# JackBot_skeem.net
KiCad netlist of a schematic drawn in Altium Designer
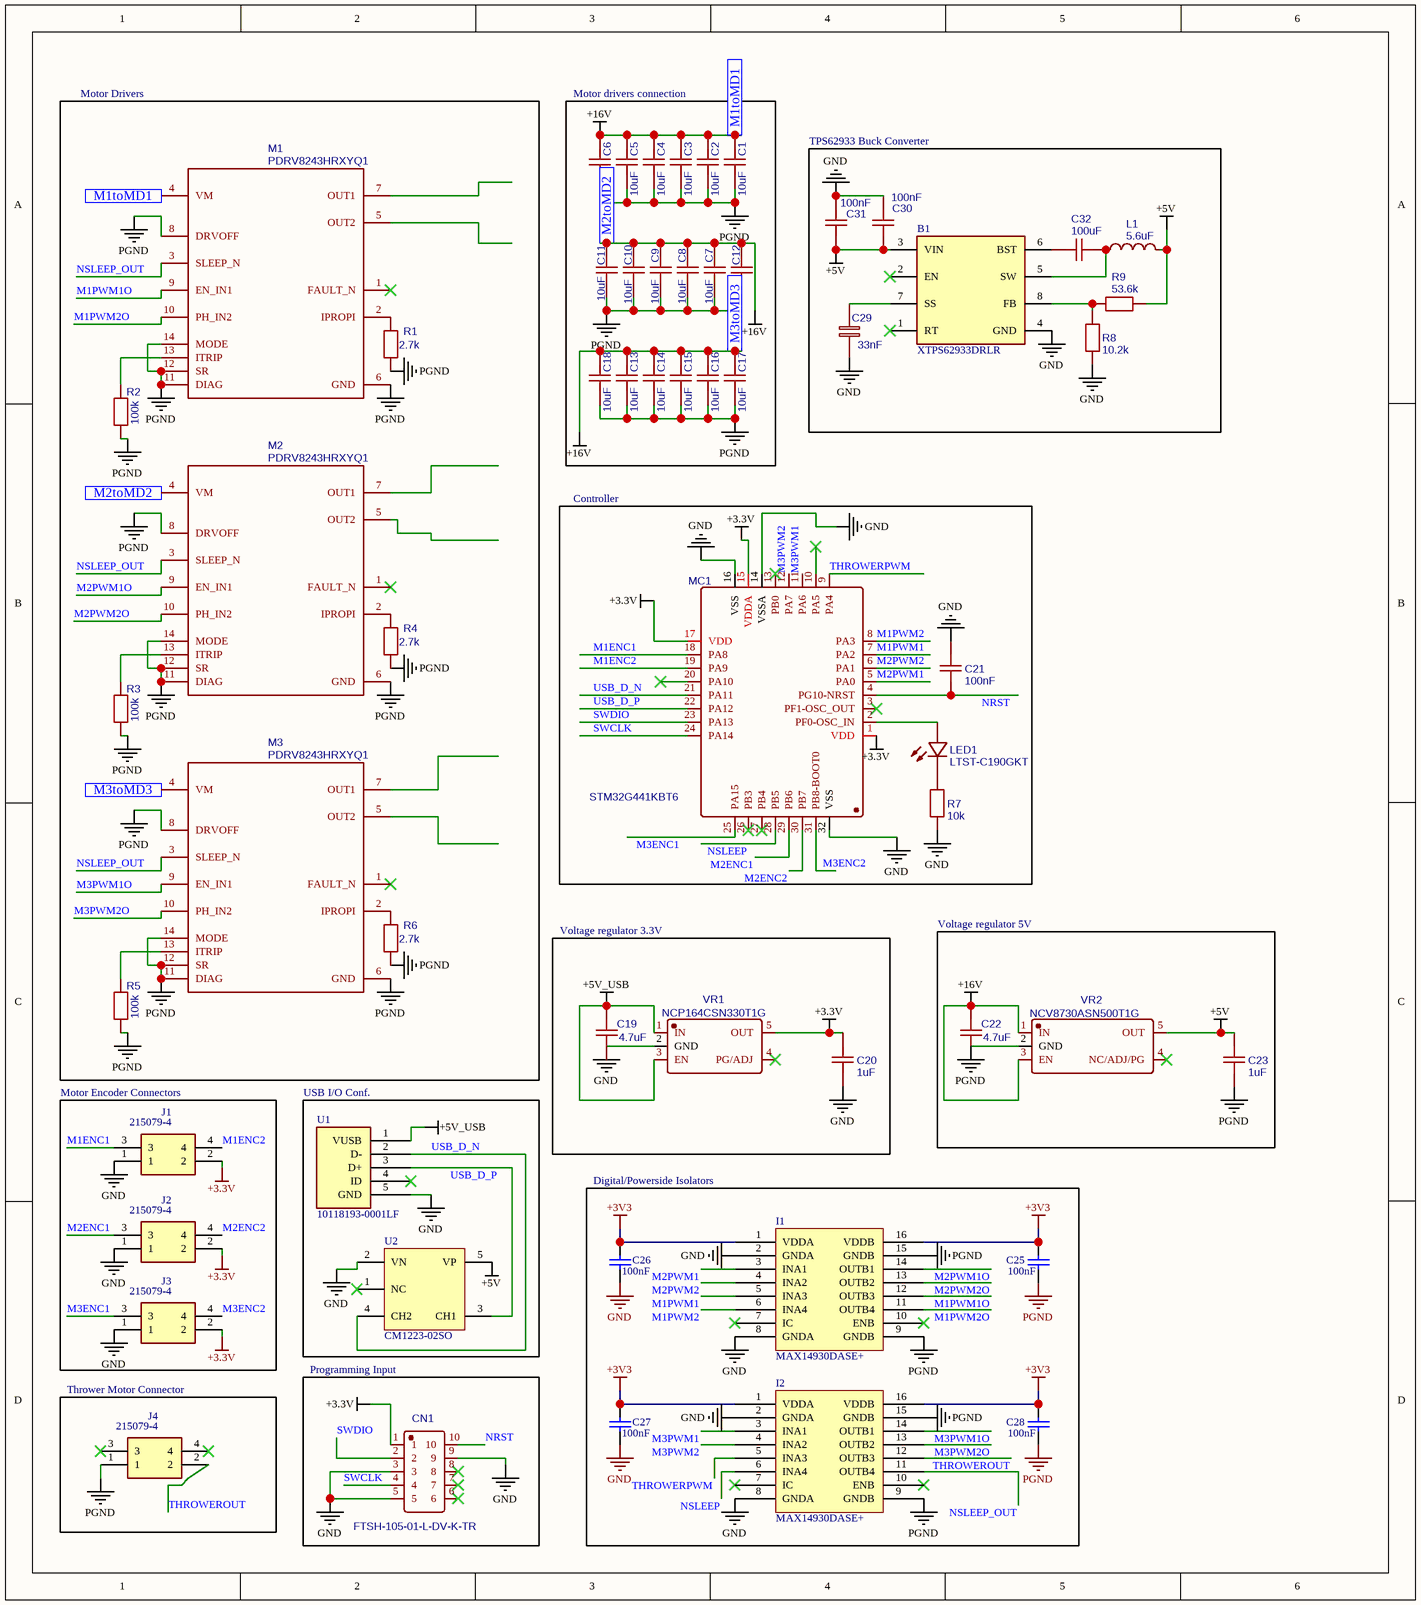
[diagram p0: JackBot_skeem.schdoc]

(export (version "E")
  (design (tool "Eeschema 10.0.6"))
  (components
    (comp (ref "B1") (value "XTPS62933DRLR") (libsource (lib "altium-import") (part "root_0_XTPS62933DRLR_")))
    (comp (ref "C1")
      (value "10uF")
      (fields (field (name "CONTRIBUTOR") "LCEDA_Lib"))
      (libsource (lib "altium-import") (part "root_3_10uF_"))
    )
    (comp (ref "C2")
      (value "10uF")
      (fields (field (name "CONTRIBUTOR") "LCEDA_Lib"))
      (libsource (lib "altium-import") (part "root_3_10uF_"))
    )
    (comp (ref "C3")
      (value "10uF")
      (fields (field (name "CONTRIBUTOR") "LCEDA_Lib"))
      (libsource (lib "altium-import") (part "root_3_10uF_"))
    )
    (comp (ref "C4")
      (value "10uF")
      (fields (field (name "CONTRIBUTOR") "LCEDA_Lib"))
      (libsource (lib "altium-import") (part "root_3_10uF_"))
    )
    (comp (ref "C5")
      (value "10uF")
      (fields (field (name "CONTRIBUTOR") "LCEDA_Lib"))
      (libsource (lib "altium-import") (part "root_3_10uF_"))
    )
    (comp (ref "C6")
      (value "10uF")
      (fields (field (name "CONTRIBUTOR") "LCEDA_Lib"))
      (libsource (lib "altium-import") (part "root_3_10uF_"))
    )
    (comp (ref "C7")
      (value "10uF")
      (fields (field (name "CONTRIBUTOR") "LCEDA_Lib"))
      (libsource (lib "") (part "root_3_10uF__1"))
    )
    (comp (ref "C8")
      (value "10uF")
      (fields (field (name "CONTRIBUTOR") "LCEDA_Lib"))
      (libsource (lib "") (part "root_3_10uF__1"))
    )
    (comp (ref "C9")
      (value "10uF")
      (fields (field (name "CONTRIBUTOR") "LCEDA_Lib"))
      (libsource (lib "") (part "root_3_10uF__1"))
    )
    (comp (ref "C10")
      (value "10uF")
      (fields (field (name "CONTRIBUTOR") "LCEDA_Lib"))
      (libsource (lib "") (part "root_3_10uF__1"))
    )
    (comp (ref "C11")
      (value "10uF")
      (fields (field (name "CONTRIBUTOR") "LCEDA_Lib"))
      (libsource (lib "") (part "root_3_10uF__1"))
    )
    (comp (ref "C12")
      (value "10uF")
      (fields (field (name "CONTRIBUTOR") "LCEDA_Lib"))
      (libsource (lib "") (part "root_3_10uF__1"))
    )
    (comp (ref "C13")
      (value "10uF")
      (fields (field (name "CONTRIBUTOR") "LCEDA_Lib"))
      (libsource (lib "altium-import") (part "root_3_10uF_"))
    )
    (comp (ref "C14")
      (value "10uF")
      (fields (field (name "CONTRIBUTOR") "LCEDA_Lib"))
      (libsource (lib "altium-import") (part "root_3_10uF_"))
    )
    (comp (ref "C15")
      (value "10uF")
      (fields (field (name "CONTRIBUTOR") "LCEDA_Lib"))
      (libsource (lib "altium-import") (part "root_3_10uF_"))
    )
    (comp (ref "C16")
      (value "10uF")
      (fields (field (name "CONTRIBUTOR") "LCEDA_Lib"))
      (libsource (lib "altium-import") (part "root_3_10uF_"))
    )
    (comp (ref "C17")
      (value "10uF")
      (fields (field (name "CONTRIBUTOR") "LCEDA_Lib"))
      (libsource (lib "altium-import") (part "root_3_10uF_"))
    )
    (comp (ref "C18")
      (value "10uF")
      (fields (field (name "CONTRIBUTOR") "LCEDA_Lib"))
      (libsource (lib "altium-import") (part "root_3_10uF_"))
    )
    (comp (ref "C19")
      (value "4.7uF")
      (fields (field (name "CONTRIBUTOR") "LCEDA_Lib"))
      (libsource (lib "altium-import") (part "root_1_4.7uF_"))
    )
    (comp (ref "C20")
      (value "1uF")
      (fields (field (name "CONTRIBUTOR") "LCEDA_Lib"))
      (libsource (lib "altium-import") (part "root_1_1uF_"))
    )
    (comp (ref "C21")
      (value "100nF")
      (fields (field (name "CONTRIBUTOR") "LCEDA_Lib"))
      (libsource (lib "altium-import") (part "root_3_100nF_"))
    )
    (comp (ref "C22")
      (value "4.7uF")
      (fields (field (name "CONTRIBUTOR") "LCEDA_Lib"))
      (libsource (lib "altium-import") (part "root_1_4.7uF_"))
    )
    (comp (ref "C23")
      (value "1uF")
      (fields (field (name "CONTRIBUTOR") "LCEDA_Lib"))
      (libsource (lib "altium-import") (part "root_1_1uF_"))
    )
    (comp (ref "C25")
      (value "100nF")
      (fields (field (name "MANUFACTURER") "Murata"))
      (libsource (lib "") (part "root_1_100nF__2"))
    )
    (comp (ref "C26")
      (value "100nF")
      (fields (field (name "MANUFACTURER") "Murata"))
      (libsource (lib "altium-import") (part "root_1_100nF_"))
    )
    (comp (ref "C27")
      (value "100nF")
      (fields (field (name "MANUFACTURER") "Murata"))
      (libsource (lib "altium-import") (part "root_1_100nF_"))
    )
    (comp (ref "C28")
      (value "100nF")
      (fields (field (name "MANUFACTURER") "Murata"))
      (libsource (lib "") (part "root_1_100nF__2"))
    )
    (comp (ref "C29")
      (value "33nF")
      (fields (field (name "CONTRIBUTOR") "LCEDA_Lib"))
      (libsource (lib "altium-import") (part "root_1_33nF_"))
    )
    (comp (ref "C30")
      (value "100nF")
      (fields (field (name "CONTRIBUTOR") "LCEDA_Lib"))
      (libsource (lib "") (part "root_1_100nF__1"))
    )
    (comp (ref "C31")
      (value "100nF")
      (fields (field (name "CONTRIBUTOR") "LCEDA_Lib"))
      (libsource (lib "") (part "root_1_100nF__1"))
    )
    (comp (ref "C32")
      (value "100uF")
      (fields (field (name "CONTRIBUTOR") "LCEDA_Lib"))
      (libsource (lib "altium-import") (part "root_2_100uF_"))
    )
    (comp (ref "CN1")
      (value "FTSH-105-01-L-DV-K-TR")
      (fields (field (name "BOM_SUPPLIER PART") "C448647") (field (name "CONTRIBUTOR") "LCSC"))
      (libsource (lib "altium-import") (part "root_0_FTSH-105-01-L-DV-K-TR_"))
    )
    (comp (ref "I1") (value "MAX14930DASE+") (libsource (lib "altium-import") (part "root_0_MAX14930DASE+_")))
    (comp (ref "I2") (value "MAX14930DASE+") (libsource (lib "altium-import") (part "root_0_MAX14930DASE+_")))
    (comp (ref "J1")
      (value "215079-4")
      (fields (field (name "MOUSER PART NUMBER") "571-215079-4"))
      (libsource (lib "altium-import") (part "root_0_215079-4_"))
    )
    (comp (ref "J2")
      (value "215079-4")
      (fields (field (name "MOUSER PART NUMBER") "571-215079-4"))
      (libsource (lib "altium-import") (part "root_0_215079-4_"))
    )
    (comp (ref "J3")
      (value "215079-4")
      (fields (field (name "MOUSER PART NUMBER") "571-215079-4"))
      (libsource (lib "altium-import") (part "root_0_215079-4_"))
    )
    (comp (ref "J4")
      (value "215079-4")
      (fields (field (name "MOUSER PART NUMBER") "571-215079-4"))
      (libsource (lib "altium-import") (part "root_0_215079-4_"))
    )
    (comp (ref "L1")
      (value "5.6uF")
      (fields (field (name "CONTRIBUTOR") "LCEDA_Lib"))
      (libsource (lib "altium-import") (part "root_0_5.6uF_"))
    )
    (comp (ref "LED1")
      (value "LTST-C190GKT")
      (fields (field (name "BOM_SUPPLIER PART") "C125093") (field (name "CONTRIBUTOR") "LCSC"))
      (libsource (lib "altium-import") (part "root_1_LTST-C190GKT_"))
    )
    (comp (ref "M1")
      (value "PDRV8243HRXYQ1")
      (fields (field (name "CONTRIBUTOR") "inkon"))
      (libsource (lib "altium-import") (part "root_0_PDRV8243HRXYQ1_"))
    )
    (comp (ref "M2")
      (value "PDRV8243HRXYQ1")
      (fields (field (name "CONTRIBUTOR") "inkon"))
      (libsource (lib "altium-import") (part "root_0_PDRV8243HRXYQ1_"))
    )
    (comp (ref "M3")
      (value "PDRV8243HRXYQ1")
      (fields (field (name "CONTRIBUTOR") "inkon"))
      (libsource (lib "altium-import") (part "root_0_PDRV8243HRXYQ1_"))
    )
    (comp (ref "MC1")
      (value "STM32G441KBT6")
      (fields (field (name "BOM_SUPPLIER PART") "C730107") (field (name "CONTRIBUTOR") "LCSC"))
      (libsource (lib "altium-import") (part "root_2_STM32G441KBT6_"))
    )
    (comp (ref "R1")
      (value "2.7k")
      (fields (field (name "CONTRIBUTOR") "LCEDA_Lib"))
      (libsource (lib "altium-import") (part "root_1_2.7k_"))
    )
    (comp (ref "R2")
      (value "100k")
      (fields (field (name "CONTRIBUTOR") "LCEDA_Lib"))
      (libsource (lib "altium-import") (part "root_1_100k_"))
    )
    (comp (ref "R3")
      (value "100k")
      (fields (field (name "CONTRIBUTOR") "LCEDA_Lib"))
      (libsource (lib "altium-import") (part "root_1_100k_"))
    )
    (comp (ref "R4")
      (value "2.7k")
      (fields (field (name "CONTRIBUTOR") "LCEDA_Lib"))
      (libsource (lib "altium-import") (part "root_1_2.7k_"))
    )
    (comp (ref "R5")
      (value "100k")
      (fields (field (name "CONTRIBUTOR") "LCEDA_Lib"))
      (libsource (lib "altium-import") (part "root_1_100k_"))
    )
    (comp (ref "R6")
      (value "2.7k")
      (fields (field (name "CONTRIBUTOR") "LCEDA_Lib"))
      (libsource (lib "altium-import") (part "root_1_2.7k_"))
    )
    (comp (ref "R7")
      (value "10k")
      (fields (field (name "CONTRIBUTOR") "LCEDA_Lib"))
      (libsource (lib "altium-import") (part "root_1_10k_"))
    )
    (comp (ref "R8")
      (value "10.2k")
      (fields (field (name "CONTRIBUTOR") "LCEDA_Lib"))
      (libsource (lib "altium-import") (part "root_1_10.2k_"))
    )
    (comp (ref "R9")
      (value "53.6k")
      (fields (field (name "CONTRIBUTOR") "LCEDA_Lib"))
      (libsource (lib "altium-import") (part "root_0_53.6k_"))
    )
    (comp (ref "U1")
      (value "*")
      (fields (field (name "MP") "10118193-0001LF") (field (name "MF") "Amphenol ICC"))
      (libsource (lib "altium-import") (part "root_0_*_"))
    )
    (comp (ref "U2")
      (value "CM1223-02SO")
      (fields (field (name "MANUFACTURER") "On Semiconductor"))
      (libsource (lib "altium-import") (part "root_2_CM1223-02SO_"))
    )
    (comp (ref "VR1")
      (value "NCP164CSN330T1G")
      (fields (field (name "BOM_SUPPLIER PART") "C892220") (field (name "CONTRIBUTOR") "LCSC"))
      (libsource (lib "altium-import") (part "root_0_NCP164CSN330T1G_"))
    )
    (comp (ref "VR2")
      (value "NCV8730ASN500T1G")
      (fields (field (name "BOM_SUPPLIER PART") "C893328") (field (name "CONTRIBUTOR") "LCSC"))
      (libsource (lib "altium-import") (part "root_0_NCV8730ASN500T1G_"))
    )
  )
  (nets
    (net (code "1") (name "+3.3V") (class "Default")
      (node (ref "C20") (pin "2") (pinfunction "2_2") (pintype "passive"))
      (node (ref "CN1") (pin "1") (pinfunction "1_1") (pintype "passive"))
      (node (ref "J1") (pin "2") (pinfunction "2_2") (pintype "passive"))
      (node (ref "J2") (pin "2") (pinfunction "2_2") (pintype "passive"))
      (node (ref "J3") (pin "2") (pinfunction "2_2") (pintype "passive"))
      (node (ref "MC1") (pin "1") (pinfunction "VDD_1") (pintype "passive"))
      (node (ref "MC1") (pin "15") (pinfunction "VDDA_15") (pintype "passive"))
      (node (ref "MC1") (pin "17") (pinfunction "VDD_17") (pintype "passive"))
      (node (ref "VR1") (pin "5") (pinfunction "OUT_5") (pintype "passive"))
    )
    (net (code "2") (name "+3V3") (class "Default")
      (node (ref "C25") (pin "2") (pinfunction "2_2") (pintype "passive"))
      (node (ref "C26") (pin "2") (pinfunction "2_2") (pintype "passive"))
      (node (ref "C27") (pin "2") (pinfunction "2_2") (pintype "passive"))
      (node (ref "C28") (pin "2") (pinfunction "2_2") (pintype "passive"))
      (node (ref "I1") (pin "1") (pinfunction "VDDA_1") (pintype "passive"))
      (node (ref "I1") (pin "16") (pinfunction "VDDB_16") (pintype "passive"))
      (node (ref "I2") (pin "1") (pinfunction "VDDA_1") (pintype "passive"))
      (node (ref "I2") (pin "16") (pinfunction "VDDB_16") (pintype "passive"))
    )
    (net (code "3") (name "+5V") (class "Default")
      (node (ref "B1") (pin "3") (pinfunction "VIN_3") (pintype "passive"))
      (node (ref "C23") (pin "2") (pinfunction "2_2") (pintype "passive"))
      (node (ref "C30") (pin "1") (pinfunction "1_1") (pintype "passive"))
      (node (ref "C31") (pin "1") (pinfunction "1_1") (pintype "passive"))
      (node (ref "L1") (pin "2") (pinfunction "2_2") (pintype "passive"))
      (node (ref "R9") (pin "2") (pinfunction "2_2") (pintype "passive"))
      (node (ref "U2") (pin "5") (pinfunction "VP_5") (pintype "passive"))
      (node (ref "VR2") (pin "5") (pinfunction "OUT_5") (pintype "passive"))
    )
    (net (code "4") (name "+5V_USB") (class "Default")
      (node (ref "C19") (pin "2") (pinfunction "2_2") (pintype "passive"))
      (node (ref "U1") (pin "1") (pinfunction "VUSB_1") (pintype "passive"))
      (node (ref "VR1") (pin "1") (pinfunction "IN_1") (pintype "passive"))
      (node (ref "VR1") (pin "3") (pinfunction "EN_3") (pintype "passive"))
    )
    (net (code "5") (name "+16V") (class "Default")
      (node (ref "C1") (pin "1") (pinfunction "1_1") (pintype "passive"))
      (node (ref "C10") (pin "1") (pinfunction "1_1") (pintype "passive"))
      (node (ref "C11") (pin "1") (pinfunction "1_1") (pintype "passive"))
      (node (ref "C12") (pin "1") (pinfunction "1_1") (pintype "passive"))
      (node (ref "C13") (pin "1") (pinfunction "1_1") (pintype "passive"))
      (node (ref "C14") (pin "1") (pinfunction "1_1") (pintype "passive"))
      (node (ref "C15") (pin "1") (pinfunction "1_1") (pintype "passive"))
      (node (ref "C16") (pin "1") (pinfunction "1_1") (pintype "passive"))
      (node (ref "C17") (pin "1") (pinfunction "1_1") (pintype "passive"))
      (node (ref "C18") (pin "1") (pinfunction "1_1") (pintype "passive"))
      (node (ref "C2") (pin "1") (pinfunction "1_1") (pintype "passive"))
      (node (ref "C22") (pin "2") (pinfunction "2_2") (pintype "passive"))
      (node (ref "C3") (pin "1") (pinfunction "1_1") (pintype "passive"))
      (node (ref "C4") (pin "1") (pinfunction "1_1") (pintype "passive"))
      (node (ref "C5") (pin "1") (pinfunction "1_1") (pintype "passive"))
      (node (ref "C6") (pin "1") (pinfunction "1_1") (pintype "passive"))
      (node (ref "C7") (pin "1") (pinfunction "1_1") (pintype "passive"))
      (node (ref "C8") (pin "1") (pinfunction "1_1") (pintype "passive"))
      (node (ref "C9") (pin "1") (pinfunction "1_1") (pintype "passive"))
      (node (ref "M1") (pin "4") (pinfunction "VM_4") (pintype "passive"))
      (node (ref "M2") (pin "4") (pinfunction "VM_4") (pintype "passive"))
      (node (ref "M3") (pin "4") (pinfunction "VM_4") (pintype "passive"))
      (node (ref "VR2") (pin "1") (pinfunction "IN_1") (pintype "passive"))
      (node (ref "VR2") (pin "3") (pinfunction "EN_3") (pintype "passive"))
    )
    (net (code "6") (name "/M1ENC1") (class "Default")
      (node (ref "J1") (pin "3") (pinfunction "3_3") (pintype "passive"))
      (node (ref "MC1") (pin "18") (pinfunction "PA8_18") (pintype "passive"))
    )
    (net (code "7") (name "/M1ENC2") (class "Default")
      (node (ref "J1") (pin "4") (pinfunction "4_4") (pintype "passive"))
      (node (ref "MC1") (pin "19") (pinfunction "PA9_19") (pintype "passive"))
    )
    (net (code "8") (name "/M1PWM1") (class "Default")
      (node (ref "I1") (pin "5") (pinfunction "INA3_5") (pintype "passive"))
      (node (ref "MC1") (pin "7") (pinfunction "PA2_7") (pintype "passive"))
    )
    (net (code "9") (name "/M1PWM1O") (class "Default")
      (node (ref "I1") (pin "12") (pinfunction "OUTB3_12") (pintype "passive"))
      (node (ref "M1") (pin "9") (pinfunction "EN_IN1_9") (pintype "passive"))
    )
    (net (code "10") (name "/M1PWM2") (class "Default")
      (node (ref "I1") (pin "6") (pinfunction "INA4_6") (pintype "passive"))
      (node (ref "MC1") (pin "8") (pinfunction "PA3_8") (pintype "passive"))
    )
    (net (code "11") (name "/M1PWM2O") (class "Default")
      (node (ref "I1") (pin "11") (pinfunction "OUTB4_11") (pintype "passive"))
      (node (ref "M1") (pin "10") (pinfunction "PH_IN2_10") (pintype "passive"))
    )
    (net (code "12") (name "/M2ENC1") (class "Default")
      (node (ref "J2") (pin "3") (pinfunction "3_3") (pintype "passive"))
      (node (ref "MC1") (pin "29") (pinfunction "PB6_29") (pintype "passive"))
    )
    (net (code "13") (name "/M2ENC2") (class "Default")
      (node (ref "J2") (pin "4") (pinfunction "4_4") (pintype "passive"))
      (node (ref "MC1") (pin "30") (pinfunction "PB7_30") (pintype "passive"))
    )
    (net (code "14") (name "/M2PWM1") (class "Default")
      (node (ref "I1") (pin "3") (pinfunction "INA1_3") (pintype "passive"))
      (node (ref "MC1") (pin "5") (pinfunction "PA0_5") (pintype "passive"))
    )
    (net (code "15") (name "/M2PWM1O") (class "Default")
      (node (ref "I1") (pin "14") (pinfunction "OUTB1_14") (pintype "passive"))
      (node (ref "M2") (pin "9") (pinfunction "EN_IN1_9") (pintype "passive"))
    )
    (net (code "16") (name "/M2PWM2") (class "Default")
      (node (ref "I1") (pin "4") (pinfunction "INA2_4") (pintype "passive"))
      (node (ref "MC1") (pin "6") (pinfunction "PA1_6") (pintype "passive"))
    )
    (net (code "17") (name "/M2PWM2O") (class "Default")
      (node (ref "I1") (pin "13") (pinfunction "OUTB2_13") (pintype "passive"))
      (node (ref "M2") (pin "10") (pinfunction "PH_IN2_10") (pintype "passive"))
    )
    (net (code "18") (name "/M3ENC1") (class "Default")
      (node (ref "J3") (pin "3") (pinfunction "3_3") (pintype "passive"))
      (node (ref "MC1") (pin "25") (pinfunction "PA15_25") (pintype "passive"))
    )
    (net (code "19") (name "/M3ENC2") (class "Default")
      (node (ref "J3") (pin "4") (pinfunction "4_4") (pintype "passive"))
      (node (ref "MC1") (pin "31") (pinfunction "PB8-BOOT0_31") (pintype "passive"))
    )
    (net (code "20") (name "/M3PWM1") (class "Default")
      (node (ref "I2") (pin "3") (pinfunction "INA1_3") (pintype "passive"))
      (node (ref "MC1") (pin "11") (pinfunction "PA6_11") (pintype "passive"))
    )
    (net (code "21") (name "/M3PWM1O") (class "Default")
      (node (ref "I2") (pin "14") (pinfunction "OUTB1_14") (pintype "passive"))
      (node (ref "M3") (pin "9") (pinfunction "EN_IN1_9") (pintype "passive"))
    )
    (net (code "22") (name "/M3PWM2") (class "Default")
      (node (ref "I2") (pin "4") (pinfunction "INA2_4") (pintype "passive"))
      (node (ref "MC1") (pin "12") (pinfunction "PA7_12") (pintype "passive"))
    )
    (net (code "23") (name "/M3PWM2O") (class "Default")
      (node (ref "I2") (pin "13") (pinfunction "OUTB2_13") (pintype "passive"))
      (node (ref "M3") (pin "10") (pinfunction "PH_IN2_10") (pintype "passive"))
    )
    (net (code "24") (name "/NRST") (class "Default")
      (node (ref "C21") (pin "2") (pinfunction "2_2") (pintype "passive"))
      (node (ref "CN1") (pin "10") (pinfunction "10_10") (pintype "passive"))
      (node (ref "MC1") (pin "4") (pinfunction "PG10-NRST_4") (pintype "passive"))
    )
    (net (code "25") (name "/NSLEEP") (class "Default")
      (node (ref "I2") (pin "6") (pinfunction "INA4_6") (pintype "passive"))
      (node (ref "MC1") (pin "28") (pinfunction "PB5_28") (pintype "passive"))
    )
    (net (code "26") (name "/NSLEEP_OUT") (class "Default")
      (node (ref "I2") (pin "11") (pinfunction "OUTB4_11") (pintype "passive"))
      (node (ref "M1") (pin "3") (pinfunction "SLEEP_N_3") (pintype "passive"))
      (node (ref "M2") (pin "3") (pinfunction "SLEEP_N_3") (pintype "passive"))
      (node (ref "M3") (pin "3") (pinfunction "SLEEP_N_3") (pintype "passive"))
    )
    (net (code "27") (name "/SWCLK") (class "Default")
      (node (ref "CN1") (pin "4") (pinfunction "4_4") (pintype "passive"))
      (node (ref "MC1") (pin "24") (pinfunction "PA14_24") (pintype "passive"))
    )
    (net (code "28") (name "/SWDIO") (class "Default")
      (node (ref "CN1") (pin "2") (pinfunction "2_2") (pintype "passive"))
      (node (ref "MC1") (pin "23") (pinfunction "PA13_23") (pintype "passive"))
    )
    (net (code "29") (name "/THROWEROUT") (class "Default")
      (node (ref "I2") (pin "12") (pinfunction "OUTB3_12") (pintype "passive"))
      (node (ref "J4") (pin "2") (pinfunction "2_2") (pintype "passive"))
    )
    (net (code "30") (name "/THROWERPWM") (class "Default")
      (node (ref "I2") (pin "5") (pinfunction "INA3_5") (pintype "passive"))
      (node (ref "MC1") (pin "9") (pinfunction "PA4_9") (pintype "passive"))
    )
    (net (code "31") (name "/USB_D_N") (class "Default")
      (node (ref "MC1") (pin "21") (pinfunction "PA11_21") (pintype "passive"))
      (node (ref "U1") (pin "2") (pinfunction "D-_2") (pintype "passive"))
      (node (ref "U2") (pin "4") (pinfunction "CH2_4") (pintype "passive"))
    )
    (net (code "32") (name "/USB_D_P") (class "Default")
      (node (ref "MC1") (pin "22") (pinfunction "PA12_22") (pintype "passive"))
      (node (ref "U1") (pin "3") (pinfunction "D+_3") (pintype "passive"))
      (node (ref "U2") (pin "3") (pinfunction "CH1_3") (pintype "passive"))
    )
    (net (code "33") (name "GND") (class "Default")
      (node (ref "B1") (pin "4") (pinfunction "GND_4") (pintype "passive"))
      (node (ref "C20") (pin "1") (pinfunction "1_1") (pintype "passive"))
      (node (ref "C21") (pin "1") (pinfunction "1_1") (pintype "passive"))
      (node (ref "C26") (pin "1") (pinfunction "1_1") (pintype "passive"))
      (node (ref "C27") (pin "1") (pinfunction "1_1") (pintype "passive"))
      (node (ref "C29") (pin "1") (pinfunction "1_1") (pintype "passive"))
      (node (ref "C30") (pin "2") (pinfunction "2_2") (pintype "passive"))
      (node (ref "C31") (pin "2") (pinfunction "2_2") (pintype "passive"))
      (node (ref "CN1") (pin "3") (pinfunction "3_3") (pintype "passive"))
      (node (ref "CN1") (pin "5") (pinfunction "5_5") (pintype "passive"))
      (node (ref "CN1") (pin "9") (pinfunction "9_9") (pintype "passive"))
      (node (ref "I1") (pin "2") (pinfunction "GNDA_2") (pintype "passive"))
      (node (ref "I1") (pin "8") (pinfunction "GNDA_8") (pintype "passive"))
      (node (ref "I2") (pin "2") (pinfunction "GNDA_2") (pintype "passive"))
      (node (ref "I2") (pin "8") (pinfunction "GNDA_8") (pintype "passive"))
      (node (ref "J1") (pin "1") (pinfunction "1_1") (pintype "passive"))
      (node (ref "J2") (pin "1") (pinfunction "1_1") (pintype "passive"))
      (node (ref "J3") (pin "1") (pinfunction "1_1") (pintype "passive"))
      (node (ref "MC1") (pin "14") (pinfunction "VSSA_14") (pintype "passive"))
      (node (ref "MC1") (pin "16") (pinfunction "VSS_16") (pintype "passive"))
      (node (ref "MC1") (pin "32") (pinfunction "VSS_32") (pintype "passive"))
      (node (ref "R7") (pin "1") (pinfunction "1_1") (pintype "passive"))
      (node (ref "R8") (pin "1") (pinfunction "1_1") (pintype "passive"))
      (node (ref "U1") (pin "5") (pinfunction "GND_5") (pintype "passive"))
      (node (ref "U2") (pin "2") (pinfunction "VN_2") (pintype "passive"))
      (node (ref "VR1") (pin "2") (pinfunction "GND_2") (pintype "passive"))
    )
    (net (code "34") (name "Net-(B1-BST)") (class "Default")
      (node (ref "B1") (pin "6") (pinfunction "BST_6") (pintype "passive"))
      (node (ref "C32") (pin "2") (pinfunction "2_2") (pintype "passive"))
    )
    (net (code "35") (name "Net-(B1-FB)") (class "Default")
      (node (ref "B1") (pin "8") (pinfunction "FB_8") (pintype "passive"))
      (node (ref "R8") (pin "2") (pinfunction "2_2") (pintype "passive"))
      (node (ref "R9") (pin "1") (pinfunction "1_1") (pintype "passive"))
    )
    (net (code "36") (name "Net-(B1-SS)") (class "Default")
      (node (ref "B1") (pin "7") (pinfunction "SS_7") (pintype "passive"))
      (node (ref "C29") (pin "2") (pinfunction "2_2") (pintype "passive"))
    )
    (net (code "37") (name "Net-(B1-SW)") (class "Default")
      (node (ref "B1") (pin "5") (pinfunction "SW_5") (pintype "passive"))
      (node (ref "C32") (pin "1") (pinfunction "1_1") (pintype "passive"))
      (node (ref "L1") (pin "1") (pinfunction "1_1") (pintype "passive"))
    )
    (net (code "38") (name "Net-(LED1-+)") (class "Default")
      (node (ref "LED1") (pin "2") (pinfunction "+_2") (pintype "passive"))
      (node (ref "MC1") (pin "2") (pinfunction "PF0-OSC_IN_2") (pintype "passive"))
    )
    (net (code "39") (name "Net-(LED1--)") (class "Default")
      (node (ref "LED1") (pin "1") (pinfunction "-_1") (pintype "passive"))
      (node (ref "R7") (pin "2") (pinfunction "2_2") (pintype "passive"))
    )
    (net (code "40") (name "Net-(M1-IPROPI)") (class "Default")
      (node (ref "M1") (pin "2") (pinfunction "IPROPI_2") (pintype "passive"))
      (node (ref "R1") (pin "2") (pinfunction "2_2") (pintype "passive"))
    )
    (net (code "41") (name "Net-(M1-ITRIP)") (class "Default")
      (node (ref "M1") (pin "13") (pinfunction "ITRIP_13") (pintype "passive"))
      (node (ref "R2") (pin "2") (pinfunction "2_2") (pintype "passive"))
    )
    (net (code "42") (name "Net-(M2-IPROPI)") (class "Default")
      (node (ref "M2") (pin "2") (pinfunction "IPROPI_2") (pintype "passive"))
      (node (ref "R4") (pin "2") (pinfunction "2_2") (pintype "passive"))
    )
    (net (code "43") (name "Net-(M2-ITRIP)") (class "Default")
      (node (ref "M2") (pin "13") (pinfunction "ITRIP_13") (pintype "passive"))
      (node (ref "R3") (pin "2") (pinfunction "2_2") (pintype "passive"))
    )
    (net (code "44") (name "Net-(M3-IPROPI)") (class "Default")
      (node (ref "M3") (pin "2") (pinfunction "IPROPI_2") (pintype "passive"))
      (node (ref "R6") (pin "2") (pinfunction "2_2") (pintype "passive"))
    )
    (net (code "45") (name "Net-(M3-ITRIP)") (class "Default")
      (node (ref "M3") (pin "13") (pinfunction "ITRIP_13") (pintype "passive"))
      (node (ref "R5") (pin "2") (pinfunction "2_2") (pintype "passive"))
    )
    (net (code "46") (name "PGND") (class "Default")
      (node (ref "C1") (pin "2") (pinfunction "2_2") (pintype "passive"))
      (node (ref "C10") (pin "2") (pinfunction "2_2") (pintype "passive"))
      (node (ref "C11") (pin "2") (pinfunction "2_2") (pintype "passive"))
      (node (ref "C12") (pin "2") (pinfunction "2_2") (pintype "passive"))
      (node (ref "C13") (pin "2") (pinfunction "2_2") (pintype "passive"))
      (node (ref "C14") (pin "2") (pinfunction "2_2") (pintype "passive"))
      (node (ref "C15") (pin "2") (pinfunction "2_2") (pintype "passive"))
      (node (ref "C16") (pin "2") (pinfunction "2_2") (pintype "passive"))
      (node (ref "C17") (pin "2") (pinfunction "2_2") (pintype "passive"))
      (node (ref "C18") (pin "2") (pinfunction "2_2") (pintype "passive"))
      (node (ref "C2") (pin "2") (pinfunction "2_2") (pintype "passive"))
      (node (ref "C23") (pin "1") (pinfunction "1_1") (pintype "passive"))
      (node (ref "C25") (pin "1") (pinfunction "1_1") (pintype "passive"))
      (node (ref "C28") (pin "1") (pinfunction "1_1") (pintype "passive"))
      (node (ref "C3") (pin "2") (pinfunction "2_2") (pintype "passive"))
      (node (ref "C4") (pin "2") (pinfunction "2_2") (pintype "passive"))
      (node (ref "C5") (pin "2") (pinfunction "2_2") (pintype "passive"))
      (node (ref "C6") (pin "2") (pinfunction "2_2") (pintype "passive"))
      (node (ref "C7") (pin "2") (pinfunction "2_2") (pintype "passive"))
      (node (ref "C8") (pin "2") (pinfunction "2_2") (pintype "passive"))
      (node (ref "C9") (pin "2") (pinfunction "2_2") (pintype "passive"))
      (node (ref "I1") (pin "15") (pinfunction "GNDB_15") (pintype "passive"))
      (node (ref "I1") (pin "9") (pinfunction "GNDB_9") (pintype "passive"))
      (node (ref "I2") (pin "15") (pinfunction "GNDB_15") (pintype "passive"))
      (node (ref "I2") (pin "9") (pinfunction "GNDB_9") (pintype "passive"))
      (node (ref "J4") (pin "1") (pinfunction "1_1") (pintype "passive"))
      (node (ref "M1") (pin "11") (pinfunction "DIAG_11") (pintype "passive"))
      (node (ref "M1") (pin "12") (pinfunction "SR_12") (pintype "passive"))
      (node (ref "M1") (pin "14") (pinfunction "MODE_14") (pintype "passive"))
      (node (ref "M1") (pin "6") (pinfunction "GND_6") (pintype "passive"))
      (node (ref "M1") (pin "8") (pinfunction "DRVOFF_8") (pintype "passive"))
      (node (ref "M2") (pin "11") (pinfunction "DIAG_11") (pintype "passive"))
      (node (ref "M2") (pin "12") (pinfunction "SR_12") (pintype "passive"))
      (node (ref "M2") (pin "14") (pinfunction "MODE_14") (pintype "passive"))
      (node (ref "M2") (pin "6") (pinfunction "GND_6") (pintype "passive"))
      (node (ref "M2") (pin "8") (pinfunction "DRVOFF_8") (pintype "passive"))
      (node (ref "M3") (pin "11") (pinfunction "DIAG_11") (pintype "passive"))
      (node (ref "M3") (pin "12") (pinfunction "SR_12") (pintype "passive"))
      (node (ref "M3") (pin "14") (pinfunction "MODE_14") (pintype "passive"))
      (node (ref "M3") (pin "6") (pinfunction "GND_6") (pintype "passive"))
      (node (ref "M3") (pin "8") (pinfunction "DRVOFF_8") (pintype "passive"))
      (node (ref "R1") (pin "1") (pinfunction "1_1") (pintype "passive"))
      (node (ref "R2") (pin "1") (pinfunction "1_1") (pintype "passive"))
      (node (ref "R3") (pin "1") (pinfunction "1_1") (pintype "passive"))
      (node (ref "R4") (pin "1") (pinfunction "1_1") (pintype "passive"))
      (node (ref "R5") (pin "1") (pinfunction "1_1") (pintype "passive"))
      (node (ref "R6") (pin "1") (pinfunction "1_1") (pintype "passive"))
      (node (ref "VR2") (pin "2") (pinfunction "GND_2") (pintype "passive"))
    )
    (net (code "47") (name "unconnected-(B1-EN-Pad2)") (class "Default")
      (node (ref "B1") (pin "2") (pinfunction "EN_2") (pintype "passive+no_connect"))
    )
    (net (code "48") (name "unconnected-(B1-RT-Pad1)") (class "Default")
      (node (ref "B1") (pin "1") (pinfunction "RT_1") (pintype "passive+no_connect"))
    )
    (net (code "49") (name "unconnected-(C19-Pad1)") (class "Default")
      (node (ref "C19") (pin "1") (pinfunction "1_1") (pintype "passive"))
    )
    (net (code "50") (name "unconnected-(C22-Pad1)") (class "Default")
      (node (ref "C22") (pin "1") (pinfunction "1_1") (pintype "passive"))
    )
    (net (code "51") (name "unconnected-(CN1-Pad6)") (class "Default")
      (node (ref "CN1") (pin "6") (pinfunction "6_6") (pintype "passive+no_connect"))
    )
    (net (code "52") (name "unconnected-(CN1-Pad7)") (class "Default")
      (node (ref "CN1") (pin "7") (pinfunction "7_7") (pintype "passive+no_connect"))
    )
    (net (code "53") (name "unconnected-(CN1-Pad8)") (class "Default")
      (node (ref "CN1") (pin "8") (pinfunction "8_8") (pintype "passive+no_connect"))
    )
    (net (code "54") (name "unconnected-(I1-ENB-Pad10)") (class "Default")
      (node (ref "I1") (pin "10") (pinfunction "ENB_10") (pintype "passive+no_connect"))
    )
    (net (code "55") (name "unconnected-(I1-IC-Pad7)") (class "Default")
      (node (ref "I1") (pin "7") (pinfunction "IC_7") (pintype "passive+no_connect"))
    )
    (net (code "56") (name "unconnected-(I2-ENB-Pad10)") (class "Default")
      (node (ref "I2") (pin "10") (pinfunction "ENB_10") (pintype "passive+no_connect"))
    )
    (net (code "57") (name "unconnected-(I2-IC-Pad7)") (class "Default")
      (node (ref "I2") (pin "7") (pinfunction "IC_7") (pintype "passive+no_connect"))
    )
    (net (code "58") (name "unconnected-(J4-Pad3)") (class "Default")
      (node (ref "J4") (pin "3") (pinfunction "3_3") (pintype "passive+no_connect"))
    )
    (net (code "59") (name "unconnected-(J4-Pad4)") (class "Default")
      (node (ref "J4") (pin "4") (pinfunction "4_4") (pintype "passive+no_connect"))
    )
    (net (code "60") (name "unconnected-(M1-FAULT_N-Pad1)") (class "Default")
      (node (ref "M1") (pin "1") (pinfunction "FAULT_N_1") (pintype "passive+no_connect"))
    )
    (net (code "61") (name "unconnected-(M1-OUT1-Pad7)") (class "Default")
      (node (ref "M1") (pin "7") (pinfunction "OUT1_7") (pintype "passive"))
    )
    (net (code "62") (name "unconnected-(M1-OUT2-Pad5)") (class "Default")
      (node (ref "M1") (pin "5") (pinfunction "OUT2_5") (pintype "passive"))
    )
    (net (code "63") (name "unconnected-(M2-FAULT_N-Pad1)") (class "Default")
      (node (ref "M2") (pin "1") (pinfunction "FAULT_N_1") (pintype "passive+no_connect"))
    )
    (net (code "64") (name "unconnected-(M2-OUT1-Pad7)") (class "Default")
      (node (ref "M2") (pin "7") (pinfunction "OUT1_7") (pintype "passive"))
    )
    (net (code "65") (name "unconnected-(M2-OUT2-Pad5)") (class "Default")
      (node (ref "M2") (pin "5") (pinfunction "OUT2_5") (pintype "passive"))
    )
    (net (code "66") (name "unconnected-(M3-FAULT_N-Pad1)") (class "Default")
      (node (ref "M3") (pin "1") (pinfunction "FAULT_N_1") (pintype "passive+no_connect"))
    )
    (net (code "67") (name "unconnected-(M3-OUT1-Pad7)") (class "Default")
      (node (ref "M3") (pin "7") (pinfunction "OUT1_7") (pintype "passive"))
    )
    (net (code "68") (name "unconnected-(M3-OUT2-Pad5)") (class "Default")
      (node (ref "M3") (pin "5") (pinfunction "OUT2_5") (pintype "passive"))
    )
    (net (code "69") (name "unconnected-(MC1-PA5-Pad10)") (class "Default")
      (node (ref "MC1") (pin "10") (pinfunction "PA5_10") (pintype "passive+no_connect"))
    )
    (net (code "70") (name "unconnected-(MC1-PA10-Pad20)") (class "Default")
      (node (ref "MC1") (pin "20") (pinfunction "PA10_20") (pintype "passive+no_connect"))
    )
    (net (code "71") (name "unconnected-(MC1-PB0-Pad13)") (class "Default")
      (node (ref "MC1") (pin "13") (pinfunction "PB0_13") (pintype "passive+no_connect"))
    )
    (net (code "72") (name "unconnected-(MC1-PB3-Pad26)") (class "Default")
      (node (ref "MC1") (pin "26") (pinfunction "PB3_26") (pintype "passive+no_connect"))
    )
    (net (code "73") (name "unconnected-(MC1-PB4-Pad27)") (class "Default")
      (node (ref "MC1") (pin "27") (pinfunction "PB4_27") (pintype "passive+no_connect"))
    )
    (net (code "74") (name "unconnected-(MC1-PF1-OSC_OUT-Pad3)") (class "Default")
      (node (ref "MC1") (pin "3") (pinfunction "PF1-OSC_OUT_3") (pintype "passive+no_connect"))
    )
    (net (code "75") (name "unconnected-(U1-ID-Pad4)") (class "Default")
      (node (ref "U1") (pin "4") (pinfunction "ID_4") (pintype "passive+no_connect"))
    )
    (net (code "76") (name "unconnected-(U2-NC-Pad1)") (class "Default")
      (node (ref "U2") (pin "1") (pinfunction "NC_1") (pintype "passive+no_connect"))
    )
    (net (code "77") (name "unconnected-(VR1-PG{slash}ADJ-Pad4)") (class "Default")
      (node (ref "VR1") (pin "4") (pinfunction "PG/ADJ_4") (pintype "passive+no_connect"))
    )
    (net (code "78") (name "unconnected-(VR2-NC{slash}ADJ{slash}PG-Pad4)") (class "Default")
      (node (ref "VR2") (pin "4") (pinfunction "NC/ADJ/PG_4") (pintype "passive+no_connect"))
    )
  )
)
